# LED_wchip.net
KiCad netlist of a schematic drawn in EAGLE
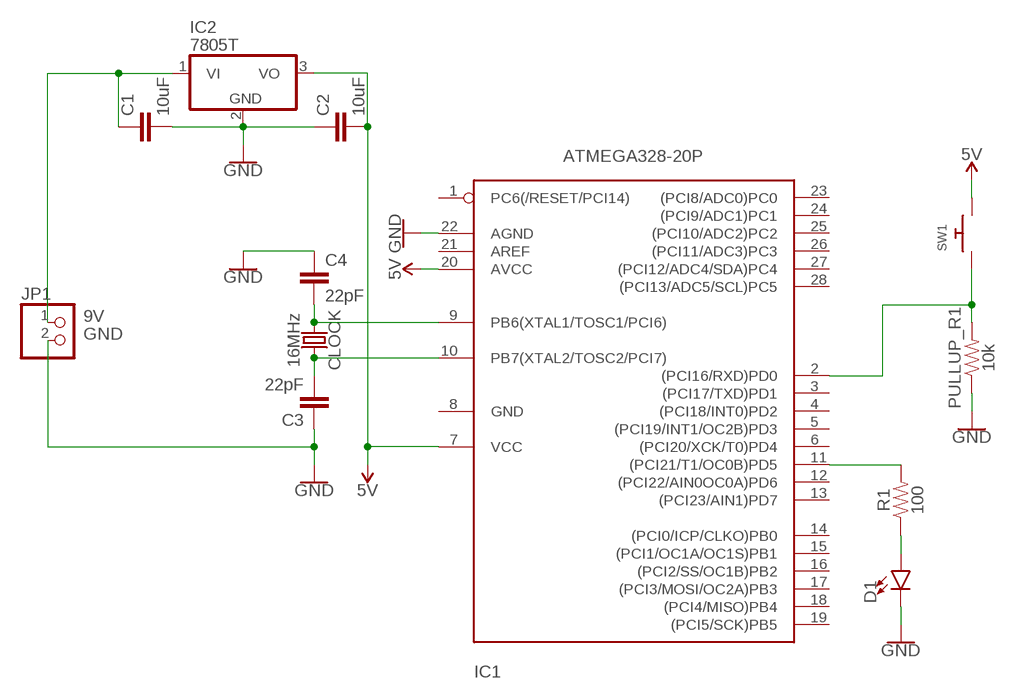
[diagram p0: schematic, sheet 1]

(export (version "E")
  (design (tool "Eeschema 10.0.6"))
  (components
    (comp (ref "C1")
      (value "10uF")
      (footprint "eagle-import:1210")
      (libsource (lib "eagle-import") (part "10UF-1210-50V-20%"))
    )
    (comp (ref "C2")
      (value "10uF")
      (footprint "eagle-import:1210")
      (libsource (lib "eagle-import") (part "10UF-1210-50V-20%"))
    )
    (comp (ref "C3")
      (value "22pF")
      (footprint "eagle-import:0603")
      (libsource (lib "eagle-import") (part "22PF-0603-50V-5%"))
    )
    (comp (ref "C4")
      (value "22pF")
      (footprint "eagle-import:0603")
      (libsource (lib "eagle-import") (part "22PF-0603-50V-5%"))
    )
    (comp (ref "CLOCK")
      (value "16MHz")
      (footprint "eagle-import:HC49US")
      (libsource (lib "eagle-import") (part "CRYSTAL-16MHZPTH-HC49US"))
    )
    (comp (ref "D1")
      (value "LED5MM")
      (footprint "eagle-import:LED_5MM")
      (libsource (lib "eagle-import") (part "LED5MM"))
    )
    (comp (ref "IC1")
      (value "ATMEGA328-20P")
      (footprint "eagle-import:DIL28-3")
      (libsource (lib "eagle-import") (part "ATMEGA328P-20"))
    )
    (comp (ref "IC2")
      (value "7805T")
      (footprint "eagle-import:TO220H")
      (libsource (lib "eagle-import") (part "78T05"))
    )
    (comp (ref "JP1")
      (value "PINHD-1X2")
      (footprint "eagle-import:1X02")
      (libsource (lib "eagle-import") (part "PINHD-1X2"))
    )
    (comp (ref "PULLUP_R1")
      (value "10k")
      (footprint "eagle-import:AXIAL-0.3")
      (libsource (lib "eagle-import") (part "10KOHM-HORIZ-1/4W-1%"))
    )
    (comp (ref "R1")
      (value "100")
      (footprint "eagle-import:AXIAL-0.3")
      (libsource (lib "eagle-import") (part "100OHM-HORIZ-1/4W-1%"))
    )
    (comp (ref "SW1")
      (value "SWITCH_PUSHBUTTONEVQ-PE")
      (footprint "eagle-import:TACT_PANA-EVQ")
      (libsource (lib "eagle-import") (part "SWITCH_PUSHBUTTONEVQ-PE"))
    )
  )
  (nets
    (net (code "1") (name "/9V") (class "Default")
      (node (ref "C1") (pin "1") (pinfunction "1_1") (pintype "passive"))
      (node (ref "IC2") (pin "1") (pinfunction "VI_1") (pintype "input"))
      (node (ref "JP1") (pin "1") (pinfunction "1_1") (pintype "passive"))
    )
    (net (code "2") (name "5V") (class "Default")
      (node (ref "C2") (pin "2") (pinfunction "2_2") (pintype "passive"))
      (node (ref "IC1") (pin "20") (pinfunction "AVCC_20") (pintype "bidirectional"))
      (node (ref "IC1") (pin "7") (pinfunction "VCC_7") (pintype "bidirectional"))
      (node (ref "IC2") (pin "3") (pinfunction "VO_3") (pintype "passive"))
      (node (ref "SW1") (pin "P$2") (pinfunction "P$2_P$2") (pintype "passive"))
    )
    (net (code "3") (name "GND") (class "Default")
      (node (ref "C1") (pin "2") (pinfunction "2_2") (pintype "passive"))
      (node (ref "C2") (pin "1") (pinfunction "1_1") (pintype "passive"))
      (node (ref "C3") (pin "1") (pinfunction "1_1") (pintype "passive"))
      (node (ref "C4") (pin "1") (pinfunction "1_1") (pintype "passive"))
      (node (ref "D1") (pin "K") (pinfunction "C_K") (pintype "passive"))
      (node (ref "IC1") (pin "22") (pinfunction "AGND_22") (pintype "bidirectional"))
      (node (ref "IC2") (pin "2") (pinfunction "GND_2") (pintype "passive"))
      (node (ref "JP1") (pin "2") (pinfunction "2_2") (pintype "passive"))
      (node (ref "PULLUP_R1") (pin "P$1") (pinfunction "1_P$1") (pintype "passive"))
    )
    (net (code "4") (name "Net-(IC1-(PCI16{slash}RXD)PD0)") (class "Default")
      (node (ref "IC1") (pin "2") (pinfunction "(PCI16/RXD)PD0_2") (pintype "bidirectional"))
      (node (ref "PULLUP_R1") (pin "P$2") (pinfunction "2_P$2") (pintype "passive"))
      (node (ref "SW1") (pin "P$1") (pinfunction "P$1_P$1") (pintype "passive"))
    )
    (net (code "5") (name "Net-(IC1-(PCI21{slash}T1{slash}OC0B)PD5)") (class "Default")
      (node (ref "IC1") (pin "11") (pinfunction "(PCI21/T1/OC0B)PD5_11") (pintype "bidirectional"))
      (node (ref "R1") (pin "P$2") (pinfunction "2_P$2") (pintype "passive"))
    )
    (net (code "6") (name "Net-(IC1-PB6(XTAL1{slash}TOSC1{slash}PCI6))") (class "Default")
      (node (ref "C4") (pin "2") (pinfunction "2_2") (pintype "passive"))
      (node (ref "CLOCK") (pin "1") (pinfunction "1_1") (pintype "passive"))
      (node (ref "IC1") (pin "9") (pinfunction "PB6(XTAL1/TOSC1/PCI6)_9") (pintype "bidirectional"))
    )
    (net (code "7") (name "Net-(IC1-PB7(XTAL2{slash}TOSC2{slash}PCI7))") (class "Default")
      (node (ref "C3") (pin "2") (pinfunction "2_2") (pintype "passive"))
      (node (ref "CLOCK") (pin "2") (pinfunction "2_2") (pintype "passive"))
      (node (ref "IC1") (pin "10") (pinfunction "PB7(XTAL2/TOSC2/PCI7)_10") (pintype "bidirectional"))
    )
    (net (code "8") (name "Net-(R1-1)") (class "Default")
      (node (ref "D1") (pin "A") (pinfunction "A_A") (pintype "passive"))
      (node (ref "R1") (pin "P$1") (pinfunction "1_P$1") (pintype "passive"))
    )
    (net (code "9") (name "unconnected-(IC1-(PCI0{slash}ICP{slash}CLKO)PB0-Pad14)") (class "Default")
      (node (ref "IC1") (pin "14") (pinfunction "(PCI0/ICP/CLKO)PB0_14") (pintype "bidirectional"))
    )
    (net (code "10") (name "unconnected-(IC1-(PCI1{slash}OC1A{slash}OC1S)PB1-Pad15)") (class "Default")
      (node (ref "IC1") (pin "15") (pinfunction "(PCI1/OC1A/OC1S)PB1_15") (pintype "bidirectional"))
    )
    (net (code "11") (name "unconnected-(IC1-(PCI2{slash}SS{slash}OC1B)PB2-Pad16)") (class "Default")
      (node (ref "IC1") (pin "16") (pinfunction "(PCI2/SS/OC1B)PB2_16") (pintype "bidirectional"))
    )
    (net (code "12") (name "unconnected-(IC1-(PCI3{slash}MOSI{slash}OC2A)PB3-Pad17)") (class "Default")
      (node (ref "IC1") (pin "17") (pinfunction "(PCI3/MOSI/OC2A)PB3_17") (pintype "bidirectional"))
    )
    (net (code "13") (name "unconnected-(IC1-(PCI4{slash}MISO)PB4-Pad18)") (class "Default")
      (node (ref "IC1") (pin "18") (pinfunction "(PCI4/MISO)PB4_18") (pintype "bidirectional"))
    )
    (net (code "14") (name "unconnected-(IC1-(PCI5{slash}SCK)PB5-Pad19)") (class "Default")
      (node (ref "IC1") (pin "19") (pinfunction "(PCI5/SCK)PB5_19") (pintype "bidirectional"))
    )
    (net (code "15") (name "unconnected-(IC1-(PCI8{slash}ADC0)PC0-Pad23)") (class "Default")
      (node (ref "IC1") (pin "23") (pinfunction "(PCI8/ADC0)PC0_23") (pintype "bidirectional"))
    )
    (net (code "16") (name "unconnected-(IC1-(PCI9{slash}ADC1)PC1-Pad24)") (class "Default")
      (node (ref "IC1") (pin "24") (pinfunction "(PCI9/ADC1)PC1_24") (pintype "bidirectional"))
    )
    (net (code "17") (name "unconnected-(IC1-(PCI10{slash}ADC2)PC2-Pad25)") (class "Default")
      (node (ref "IC1") (pin "25") (pinfunction "(PCI10/ADC2)PC2_25") (pintype "bidirectional"))
    )
    (net (code "18") (name "unconnected-(IC1-(PCI11{slash}ADC3)PC3-Pad26)") (class "Default")
      (node (ref "IC1") (pin "26") (pinfunction "(PCI11/ADC3)PC3_26") (pintype "bidirectional"))
    )
    (net (code "19") (name "unconnected-(IC1-(PCI12{slash}ADC4{slash}SDA)PC4-Pad27)") (class "Default")
      (node (ref "IC1") (pin "27") (pinfunction "(PCI12/ADC4/SDA)PC4_27") (pintype "bidirectional"))
    )
    (net (code "20") (name "unconnected-(IC1-(PCI13{slash}ADC5{slash}SCL)PC5-Pad28)") (class "Default")
      (node (ref "IC1") (pin "28") (pinfunction "(PCI13/ADC5/SCL)PC5_28") (pintype "bidirectional"))
    )
    (net (code "21") (name "unconnected-(IC1-(PCI17{slash}TXD)PD1-Pad3)") (class "Default")
      (node (ref "IC1") (pin "3") (pinfunction "(PCI17/TXD)PD1_3") (pintype "bidirectional"))
    )
    (net (code "22") (name "unconnected-(IC1-(PCI18{slash}INT0)PD2-Pad4)") (class "Default")
      (node (ref "IC1") (pin "4") (pinfunction "(PCI18/INT0)PD2_4") (pintype "bidirectional"))
    )
    (net (code "23") (name "unconnected-(IC1-(PCI19{slash}INT1{slash}OC2B)PD3-Pad5)") (class "Default")
      (node (ref "IC1") (pin "5") (pinfunction "(PCI19/INT1/OC2B)PD3_5") (pintype "bidirectional"))
    )
    (net (code "24") (name "unconnected-(IC1-(PCI20{slash}XCK{slash}T0)PD4-Pad6)") (class "Default")
      (node (ref "IC1") (pin "6") (pinfunction "(PCI20/XCK/T0)PD4_6") (pintype "bidirectional"))
    )
    (net (code "25") (name "unconnected-(IC1-(PCI22{slash}AIN0OC0A)PD6-Pad12)") (class "Default")
      (node (ref "IC1") (pin "12") (pinfunction "(PCI22/AIN0OC0A)PD6_12") (pintype "bidirectional"))
    )
    (net (code "26") (name "unconnected-(IC1-(PCI23{slash}AIN1)PD7-Pad13)") (class "Default")
      (node (ref "IC1") (pin "13") (pinfunction "(PCI23/AIN1)PD7_13") (pintype "bidirectional"))
    )
    (net (code "27") (name "unconnected-(IC1-AREF-Pad21)") (class "Default")
      (node (ref "IC1") (pin "21") (pinfunction "AREF_21") (pintype "bidirectional"))
    )
    (net (code "28") (name "unconnected-(IC1-GND-Pad8)") (class "Default")
      (node (ref "IC1") (pin "8") (pinfunction "GND_8") (pintype "bidirectional"))
    )
    (net (code "29") (name "unconnected-(IC1-PC6({slash}RESET{slash}PCI14)-Pad1)") (class "Default")
      (node (ref "IC1") (pin "1") (pinfunction "PC6(/RESET/PCI14)_1") (pintype "bidirectional"))
    )
  )
)
